# dc-driver.net
KiCad netlist of a schematic drawn in EAGLE
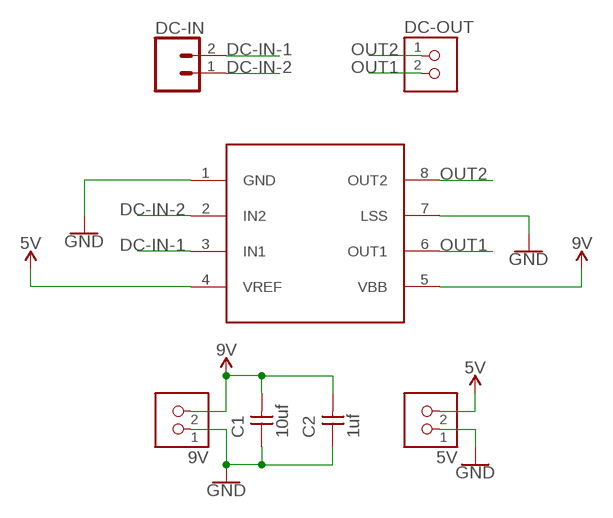
[diagram p0: schematic, sheet 1]

(export (version "E")
  (design (tool "Eeschema 10.0.6"))
  (components
    (comp (ref "5V")
      (value "TERM-1X02-FABLAB")
      (footprint "eagle-import:ED555DS-2DS")
      (libsource (lib "eagle-import") (part "TERM-1X02-FABLAB"))
    )
    (comp (ref "9V")
      (value "TERM-1X02-FABLAB")
      (footprint "eagle-import:ED555DS-2DS")
      (libsource (lib "eagle-import") (part "TERM-1X02-FABLAB"))
    )
    (comp (ref "C1")
      (value "10uf")
      (footprint "eagle-import:C1206FAB")
      (libsource (lib "eagle-import") (part "CAP-UNPOLARIZEDFAB"))
    )
    (comp (ref "C2")
      (value "1uf")
      (footprint "eagle-import:C1206FAB")
      (libsource (lib "eagle-import") (part "CAP-UNPOLARIZEDFAB"))
    )
    (comp (ref "DC-IN")
      (value "CONN_021X02_NO_SILK")
      (footprint "eagle-import:1X02_NO_SILK")
      (libsource (lib "eagle-import") (part "CONN_021X02_NO_SILK"))
    )
    (comp (ref "DC-OUT")
      (value "TERM-1X02-FABLAB")
      (footprint "eagle-import:ED555DS-2DS")
      (libsource (lib "eagle-import") (part "TERM-1X02-FABLAB"))
    )
    (comp (ref "U$1")
      (value "A4953")
      (footprint "eagle-import:SOIC8")
      (libsource (lib "eagle-import") (part "A4953-H-BRIDGE-MOTOR-DRIVER"))
    )
  )
  (nets
    (net (code "1") (name "/DC-IN-1") (class "Default")
      (node (ref "DC-IN") (pin "2") (pinfunction "2_2") (pintype "passive"))
      (node (ref "U$1") (pin "3") (pinfunction "IN1_3") (pintype "bidirectional"))
    )
    (net (code "2") (name "/DC-IN-2") (class "Default")
      (node (ref "DC-IN") (pin "1") (pinfunction "1_1") (pintype "passive"))
      (node (ref "U$1") (pin "2") (pinfunction "IN2_2") (pintype "bidirectional"))
    )
    (net (code "3") (name "/OUT1") (class "Default")
      (node (ref "DC-OUT") (pin "2") (pinfunction "2_2") (pintype "passive"))
      (node (ref "U$1") (pin "6") (pinfunction "OUT1_6") (pintype "bidirectional"))
    )
    (net (code "4") (name "/OUT2") (class "Default")
      (node (ref "DC-OUT") (pin "1") (pinfunction "1_1") (pintype "passive"))
      (node (ref "U$1") (pin "8") (pinfunction "OUT2_8") (pintype "bidirectional"))
    )
    (net (code "5") (name "5V") (class "Default")
      (node (ref "5V") (pin "2") (pinfunction "2_2") (pintype "passive"))
      (node (ref "U$1") (pin "4") (pinfunction "VREF_4") (pintype "bidirectional"))
    )
    (net (code "6") (name "9V") (class "Default")
      (node (ref "9V") (pin "2") (pinfunction "2_2") (pintype "passive"))
      (node (ref "C1") (pin "2") (pinfunction "2_2") (pintype "passive"))
      (node (ref "C2") (pin "2") (pinfunction "2_2") (pintype "passive"))
      (node (ref "U$1") (pin "5") (pinfunction "VBB_5") (pintype "bidirectional"))
    )
    (net (code "7") (name "GND") (class "Default")
      (node (ref "5V") (pin "1") (pinfunction "1_1") (pintype "passive"))
      (node (ref "9V") (pin "1") (pinfunction "1_1") (pintype "passive"))
      (node (ref "C1") (pin "1") (pinfunction "1_1") (pintype "passive"))
      (node (ref "C2") (pin "1") (pinfunction "1_1") (pintype "passive"))
      (node (ref "U$1") (pin "1") (pinfunction "GND_1") (pintype "bidirectional"))
      (node (ref "U$1") (pin "7") (pinfunction "LSS_7") (pintype "bidirectional"))
    )
  )
)
